# CON_PCIe_X4.net
KiCad netlist of a schematic drawn in Altium Designer
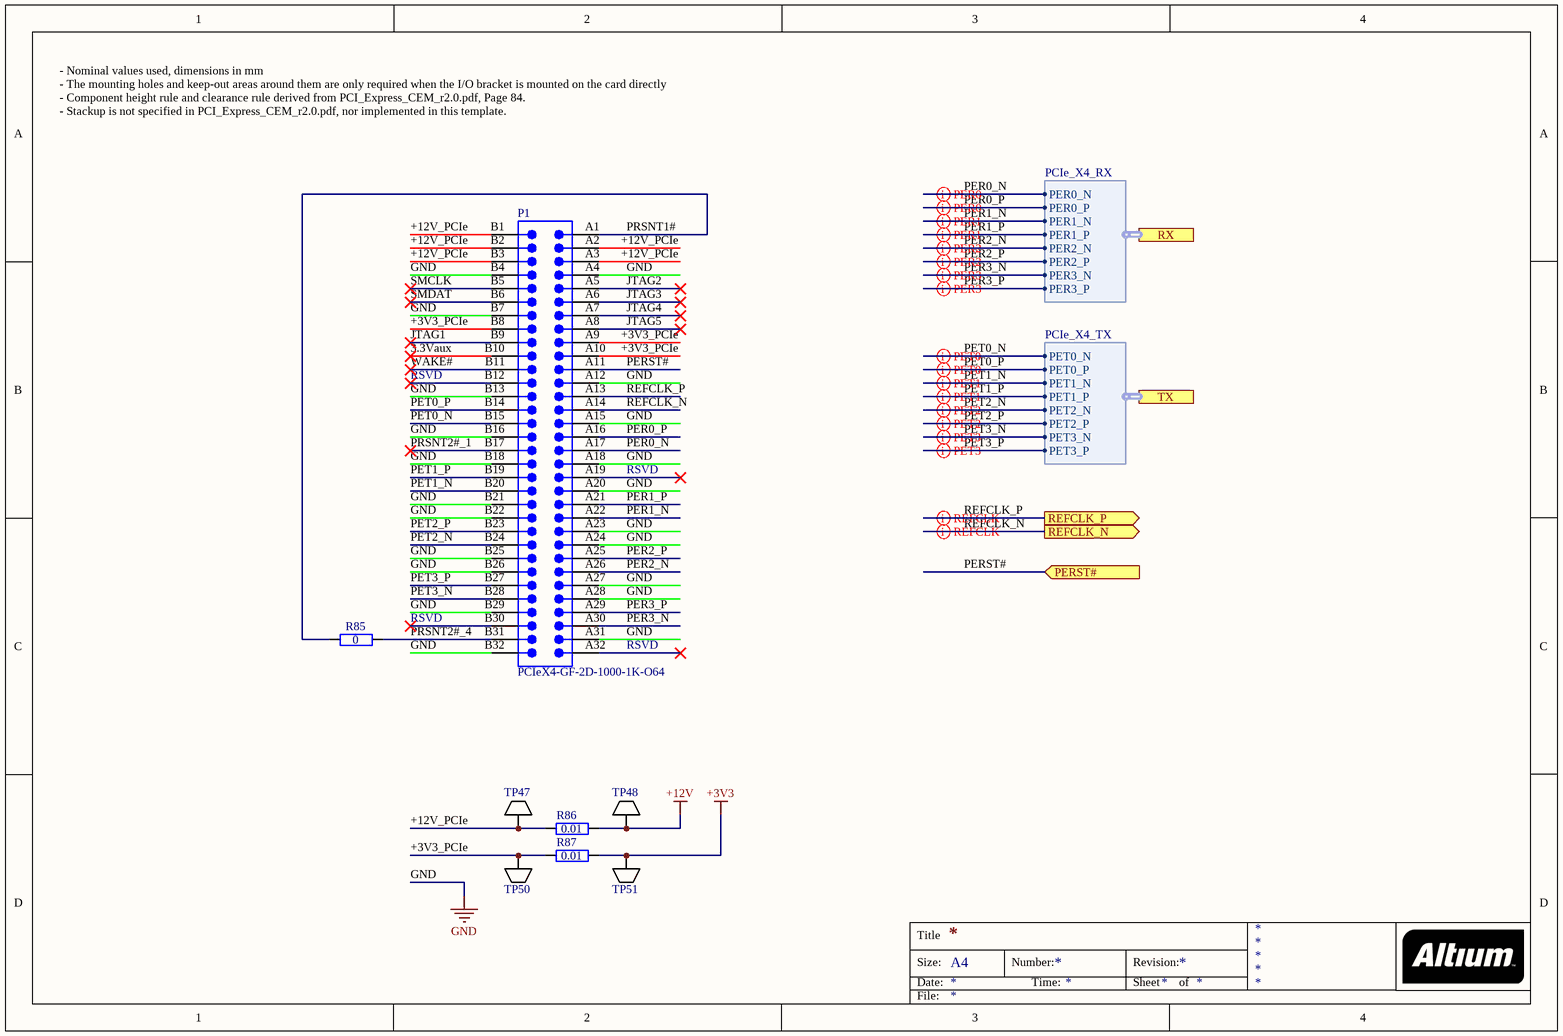
[diagram p0: CON_PCIe_X4.SchDoc]

(export (version "E")
  (design (tool "Eeschema 10.0.6"))
  (components
    (comp (ref "P1")
      (value "PCIeX4-GF-2D-1000-1K-O64")
      (footprint "PCIeX4-GF-2D-1000-1K-O64")
      (description "Golden finger, PCIeX4, Dual, Opposite, Pitch 1mm, 64-Position")
      (fields (field (name "PUBLISHER") "Altium"))
      (libsource (lib "Altium Content Vault") (part "PCIeX4-GF-2D-1000-1K-O64"))
    )
    (comp (ref "R85")
      (value "0")
      (footprint "GEN_R_0402")
      (libsource (lib "DSO") (part "RES 0 OHM 1/16W 0402"))
    )
    (comp (ref "R86")
      (value "0.01")
      (footprint "GEN_R_0603")
      (fields (field (name "TOLERANCE") "1%"))
      (libsource (lib "DSO") (part "RES 0.01 OHM 1% 1/4W 0603"))
    )
    (comp (ref "R87")
      (value "0.01")
      (footprint "GEN_R_0603")
      (fields (field (name "TOLERANCE") "1%"))
      (libsource (lib "DSO") (part "RES 0.01 OHM 1% 1/4W 0603"))
    )
    (comp (ref "TP47")
      (value "5015")
      (footprint "KEY_5015")
      (libsource (lib "DSO") (part "TP KEYSTONE 5015"))
    )
    (comp (ref "TP48")
      (value "5015")
      (footprint "KEY_5015")
      (libsource (lib "DSO") (part "TP KEYSTONE 5015"))
    )
    (comp (ref "TP50")
      (value "5015")
      (footprint "KEY_5015")
      (libsource (lib "DSO") (part "TP KEYSTONE 5015"))
    )
    (comp (ref "TP51")
      (value "5015")
      (footprint "KEY_5015")
      (libsource (lib "DSO") (part "TP KEYSTONE 5015"))
    )
  )
  (nets
    (net (code "3") (name "+3V3") (class "Default")
      (node (ref "R87") (pin "2") (pinfunction "2_2") (pintype "passive"))
      (node (ref "TP51") (pin "1") (pinfunction "1_1") (pintype "passive"))
    )
    (net (code "4") (name "+12V") (class "Default")
      (node (ref "R86") (pin "2") (pinfunction "2_2") (pintype "passive"))
      (node (ref "TP48") (pin "1") (pinfunction "1_1") (pintype "passive"))
    )
    (net (code "5") (name "/+3V3_PCIe") (class "Default")
      (node (ref "P1") (pin "A10") (pinfunction "A10_A10") (pintype "passive"))
      (node (ref "P1") (pin "A9") (pinfunction "A9_A9") (pintype "passive"))
      (node (ref "P1") (pin "B8") (pinfunction "B8_B8") (pintype "passive"))
      (node (ref "R87") (pin "1") (pinfunction "1_1") (pintype "passive"))
      (node (ref "TP50") (pin "1") (pinfunction "1_1") (pintype "passive"))
    )
    (net (code "6") (name "/+12V_PCIe") (class "Default")
      (node (ref "P1") (pin "A2") (pinfunction "A2_A2") (pintype "passive"))
      (node (ref "P1") (pin "A3") (pinfunction "A3_A3") (pintype "passive"))
      (node (ref "P1") (pin "B1") (pinfunction "B1_B1") (pintype "passive"))
      (node (ref "P1") (pin "B2") (pinfunction "B2_B2") (pintype "passive"))
      (node (ref "P1") (pin "B3") (pinfunction "B3_B3") (pintype "passive"))
      (node (ref "R86") (pin "1") (pinfunction "1_1") (pintype "passive"))
      (node (ref "TP47") (pin "1") (pinfunction "1_1") (pintype "passive"))
    )
    (net (code "7") (name "/3.3Vaux") (class "Default")
      (node (ref "P1") (pin "B10") (pinfunction "B10_B10") (pintype "passive+no_connect"))
    )
    (net (code "8") (name "/JTAG1") (class "Default")
      (node (ref "P1") (pin "B9") (pinfunction "B9_B9") (pintype "passive+no_connect"))
    )
    (net (code "9") (name "/JTAG2") (class "Default")
      (node (ref "P1") (pin "A5") (pinfunction "A5_A5") (pintype "passive+no_connect"))
    )
    (net (code "10") (name "/JTAG3") (class "Default")
      (node (ref "P1") (pin "A6") (pinfunction "A6_A6") (pintype "passive+no_connect"))
    )
    (net (code "11") (name "/JTAG4") (class "Default")
      (node (ref "P1") (pin "A7") (pinfunction "A7_A7") (pintype "passive+no_connect"))
    )
    (net (code "12") (name "/JTAG5") (class "Default")
      (node (ref "P1") (pin "A8") (pinfunction "A8_A8") (pintype "passive+no_connect"))
    )
    (net (code "13") (name "/PER0_N") (class "Default")
      (node (ref "P1") (pin "A17") (pinfunction "A17_A17") (pintype "passive"))
    )
    (net (code "14") (name "/PER0_P") (class "Default")
      (node (ref "P1") (pin "A16") (pinfunction "A16_A16") (pintype "passive"))
    )
    (net (code "15") (name "/PER1_N") (class "Default")
      (node (ref "P1") (pin "A22") (pinfunction "A22_A22") (pintype "passive"))
    )
    (net (code "16") (name "/PER1_P") (class "Default")
      (node (ref "P1") (pin "A21") (pinfunction "A21_A21") (pintype "passive"))
    )
    (net (code "17") (name "/PER2_N") (class "Default")
      (node (ref "P1") (pin "A26") (pinfunction "A26_A26") (pintype "passive"))
    )
    (net (code "18") (name "/PER2_P") (class "Default")
      (node (ref "P1") (pin "A25") (pinfunction "A25_A25") (pintype "passive"))
    )
    (net (code "19") (name "/PER3_N") (class "Default")
      (node (ref "P1") (pin "A30") (pinfunction "A30_A30") (pintype "passive"))
    )
    (net (code "20") (name "/PER3_P") (class "Default")
      (node (ref "P1") (pin "A29") (pinfunction "A29_A29") (pintype "passive"))
    )
    (net (code "21") (name "/PERST#") (class "Default")
      (node (ref "P1") (pin "A11") (pinfunction "A11_A11") (pintype "passive"))
    )
    (net (code "22") (name "/PET0_N") (class "Default")
      (node (ref "P1") (pin "B15") (pinfunction "B15_B15") (pintype "passive"))
    )
    (net (code "23") (name "/PET0_P") (class "Default")
      (node (ref "P1") (pin "B14") (pinfunction "B14_B14") (pintype "passive"))
    )
    (net (code "24") (name "/PET1_N") (class "Default")
      (node (ref "P1") (pin "B20") (pinfunction "B20_B20") (pintype "passive"))
    )
    (net (code "25") (name "/PET1_P") (class "Default")
      (node (ref "P1") (pin "B19") (pinfunction "B19_B19") (pintype "passive"))
    )
    (net (code "26") (name "/PET2_N") (class "Default")
      (node (ref "P1") (pin "B24") (pinfunction "B24_B24") (pintype "passive"))
    )
    (net (code "27") (name "/PET2_P") (class "Default")
      (node (ref "P1") (pin "B23") (pinfunction "B23_B23") (pintype "passive"))
    )
    (net (code "28") (name "/PET3_N") (class "Default")
      (node (ref "P1") (pin "B28") (pinfunction "B28_B28") (pintype "passive"))
    )
    (net (code "29") (name "/PET3_P") (class "Default")
      (node (ref "P1") (pin "B27") (pinfunction "B27_B27") (pintype "passive"))
    )
    (net (code "30") (name "/PRSNT1#") (class "Default")
      (node (ref "P1") (pin "A1") (pinfunction "A1_A1") (pintype "passive"))
      (node (ref "R85") (pin "1") (pinfunction "1_1") (pintype "passive"))
    )
    (net (code "31") (name "/PRSNT2#_1") (class "Default")
      (node (ref "P1") (pin "B17") (pinfunction "B17_B17") (pintype "passive+no_connect"))
    )
    (net (code "32") (name "/PRSNT2#_4") (class "Default")
      (node (ref "P1") (pin "B31") (pinfunction "B31_B31") (pintype "passive"))
      (node (ref "R85") (pin "2") (pinfunction "2_2") (pintype "passive"))
    )
    (net (code "33") (name "/REFCLK_N") (class "Default")
      (node (ref "P1") (pin "A14") (pinfunction "A14_A14") (pintype "passive"))
    )
    (net (code "34") (name "/REFCLK_P") (class "Default")
      (node (ref "P1") (pin "A13") (pinfunction "A13_A13") (pintype "passive"))
    )
    (net (code "35") (name "/SMCLK") (class "Default")
      (node (ref "P1") (pin "B5") (pinfunction "B5_B5") (pintype "passive+no_connect"))
    )
    (net (code "36") (name "/SMDAT") (class "Default")
      (node (ref "P1") (pin "B6") (pinfunction "B6_B6") (pintype "passive+no_connect"))
    )
    (net (code "37") (name "/WAKE#") (class "Default")
      (node (ref "P1") (pin "B11") (pinfunction "B11_B11") (pintype "passive+no_connect"))
    )
    (net (code "40") (name "GND") (class "Default")
      (node (ref "P1") (pin "A12") (pinfunction "A12_A12") (pintype "passive"))
      (node (ref "P1") (pin "A15") (pinfunction "A15_A15") (pintype "passive"))
      (node (ref "P1") (pin "A18") (pinfunction "A18_A18") (pintype "passive"))
      (node (ref "P1") (pin "A20") (pinfunction "A20_A20") (pintype "passive"))
      (node (ref "P1") (pin "A23") (pinfunction "A23_A23") (pintype "passive"))
      (node (ref "P1") (pin "A24") (pinfunction "A24_A24") (pintype "passive"))
      (node (ref "P1") (pin "A27") (pinfunction "A27_A27") (pintype "passive"))
      (node (ref "P1") (pin "A28") (pinfunction "A28_A28") (pintype "passive"))
      (node (ref "P1") (pin "A31") (pinfunction "A31_A31") (pintype "passive"))
      (node (ref "P1") (pin "A4") (pinfunction "A4_A4") (pintype "passive"))
      (node (ref "P1") (pin "B13") (pinfunction "B13_B13") (pintype "passive"))
      (node (ref "P1") (pin "B16") (pinfunction "B16_B16") (pintype "passive"))
      (node (ref "P1") (pin "B18") (pinfunction "B18_B18") (pintype "passive"))
      (node (ref "P1") (pin "B21") (pinfunction "B21_B21") (pintype "passive"))
      (node (ref "P1") (pin "B22") (pinfunction "B22_B22") (pintype "passive"))
      (node (ref "P1") (pin "B25") (pinfunction "B25_B25") (pintype "passive"))
      (node (ref "P1") (pin "B26") (pinfunction "B26_B26") (pintype "passive"))
      (node (ref "P1") (pin "B29") (pinfunction "B29_B29") (pintype "passive"))
      (node (ref "P1") (pin "B32") (pinfunction "B32_B32") (pintype "passive"))
      (node (ref "P1") (pin "B4") (pinfunction "B4_B4") (pintype "passive"))
      (node (ref "P1") (pin "B7") (pinfunction "B7_B7") (pintype "passive"))
    )
    (net (code "41") (name "unconnected-(P1-PadA19)") (class "Default")
      (node (ref "P1") (pin "A19") (pinfunction "A19_A19") (pintype "passive+no_connect"))
    )
    (net (code "42") (name "unconnected-(P1-PadA32)") (class "Default")
      (node (ref "P1") (pin "A32") (pinfunction "A32_A32") (pintype "passive+no_connect"))
    )
    (net (code "43") (name "unconnected-(P1-PadB12)") (class "Default")
      (node (ref "P1") (pin "B12") (pinfunction "B12_B12") (pintype "passive+no_connect"))
    )
    (net (code "44") (name "unconnected-(P1-PadB30)") (class "Default")
      (node (ref "P1") (pin "B30") (pinfunction "B30_B30") (pintype "passive+no_connect"))
    )
  )
)
